# CW312_K82.net
KiCad netlist of a schematic drawn in Altium Designer
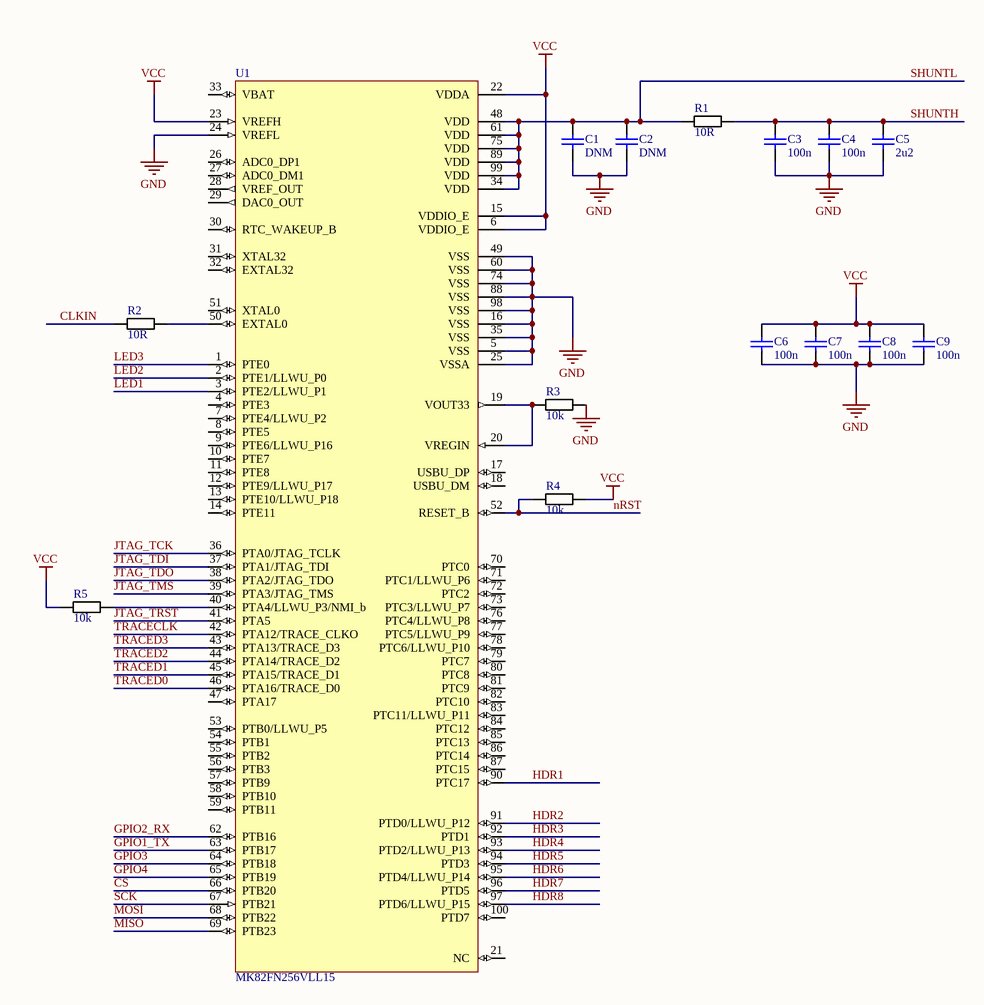
[diagram p0: CW312_K82.SchDoc]

(export (version "E")
  (design (tool "Eeschema 10.0.6"))
  (components
    (comp (ref "C1")
      (value "DNM")
      (footprint "CAPC0603_M")
      (fields (field (name "PART NUMBER") "CCHIP-100n-0603"))
      (libsource (lib "NewAE_AltiumLib") (part "CAP"))
    )
    (comp (ref "C2")
      (value "DNM")
      (footprint "CAPC0603_M")
      (fields (field (name "PART NUMBER") "CCHIP-100n-0603"))
      (libsource (lib "NewAE_AltiumLib") (part "CAP"))
    )
    (comp (ref "C3")
      (value "100n")
      (footprint "CAPC0603_M")
      (description "100n, 0603")
      (fields (field (name "PART NUMBER") "CCHIP-100n-0603"))
      (libsource (lib "NewAE_AltiumLib") (part "CAP"))
    )
    (comp (ref "C4")
      (value "100n")
      (footprint "CAPC0603_M")
      (description "100n, 0603")
      (fields (field (name "PART NUMBER") "CCHIP-100n-0603"))
      (libsource (lib "NewAE_AltiumLib") (part "CAP"))
    )
    (comp (ref "C5")
      (value "2u2")
      (footprint "CAPC0603_M")
      (description "2u2, 0603")
      (fields (field (name "PART NUMBER") "CCHIP-2u2-0603"))
      (libsource (lib "NewAE_AltiumLib") (part "CAP"))
    )
    (comp (ref "C6")
      (value "100n")
      (footprint "CAPC0603_M")
      (description "100n, 0603")
      (fields (field (name "PART NUMBER") "CCHIP-100n-0603"))
      (libsource (lib "NewAE_AltiumLib") (part "CAP"))
    )
    (comp (ref "C7")
      (value "100n")
      (footprint "CAPC0603_M")
      (description "100n, 0603")
      (fields (field (name "PART NUMBER") "CCHIP-100n-0603"))
      (libsource (lib "NewAE_AltiumLib") (part "CAP"))
    )
    (comp (ref "C8")
      (value "100n")
      (footprint "CAPC0603_M")
      (description "100n, 0603")
      (fields (field (name "PART NUMBER") "CCHIP-100n-0603"))
      (libsource (lib "NewAE_AltiumLib") (part "CAP"))
    )
    (comp (ref "C9")
      (value "100n")
      (footprint "CAPC0603_M")
      (description "100n, 0603")
      (fields (field (name "PART NUMBER") "CCHIP-100n-0603"))
      (libsource (lib "NewAE_AltiumLib") (part "CAP"))
    )
    (comp (ref "R1")
      (value "10R")
      (footprint "RESC1608X55N")
      (description "10R res, 0603, 1%, 1/10W")
      (fields (field (name "PART NUMBER") "RCHIP-10R-0603") (field (name "TOLERANCE") "1%"))
      (libsource (lib "NewAE_AltiumLib") (part "RES-EU"))
    )
    (comp (ref "R2")
      (value "10R")
      (footprint "RESC1608X55N")
      (description "10R res, 0603, 1%, 1/10W")
      (fields (field (name "PART NUMBER") "RCHIP-10R-0603") (field (name "TOLERANCE") "1%"))
      (libsource (lib "NewAE_AltiumLib") (part "RES-EU"))
    )
    (comp (ref "R3")
      (value "10k")
      (footprint "RESC1608X55N")
      (description "10k res, 0603, 1%, 1/10W")
      (fields (field (name "PART NUMBER") "RCHIP-10K-0603") (field (name "TOLERANCE") "1%"))
      (libsource (lib "NewAE_AltiumLib") (part "RES-EU"))
    )
    (comp (ref "R4")
      (value "10k")
      (footprint "RESC1608X55N")
      (description "10k res, 0603, 1%, 1/10W")
      (fields (field (name "PART NUMBER") "RCHIP-10K-0603") (field (name "TOLERANCE") "1%"))
      (libsource (lib "NewAE_AltiumLib") (part "RES-EU"))
    )
    (comp (ref "R5")
      (value "10k")
      (footprint "RESC1608X55N")
      (description "10k res, 0603, 1%, 1/10W")
      (fields (field (name "PART NUMBER") "RCHIP-10K-0603") (field (name "TOLERANCE") "1%"))
      (libsource (lib "NewAE_AltiumLib") (part "RES-EU"))
    )
    (comp (ref "U1")
      (value "MK82FN256VLL15")
      (footprint "SQFP50P1600X1600X170-100N")
      (libsource (lib "NewAE_AltiumLib") (part "MK82FN256VLL15"))
    )
  )
  (nets
    (net (code "1") (name "/CLKIN") (class "Default")
      (node (ref "R2") (pin "1") (pinfunction "1_1") (pintype "passive"))
    )
    (net (code "2") (name "/CS") (class "Default")
      (node (ref "U1") (pin "66") (pinfunction "PTB20_66") (pintype "bidirectional"))
    )
    (net (code "3") (name "/GPIO1_TX") (class "Default")
      (node (ref "U1") (pin "63") (pinfunction "PTB17_63") (pintype "bidirectional"))
    )
    (net (code "4") (name "/GPIO2_RX") (class "Default")
      (node (ref "U1") (pin "62") (pinfunction "PTB16_62") (pintype "bidirectional"))
    )
    (net (code "5") (name "/GPIO3") (class "Default")
      (node (ref "U1") (pin "64") (pinfunction "PTB18_64") (pintype "bidirectional"))
    )
    (net (code "6") (name "/GPIO4") (class "Default")
      (node (ref "U1") (pin "65") (pinfunction "PTB19_65") (pintype "bidirectional"))
    )
    (net (code "7") (name "/HDR1") (class "Default")
      (node (ref "U1") (pin "90") (pinfunction "PTC17_90") (pintype "bidirectional"))
    )
    (net (code "8") (name "/HDR2") (class "Default")
      (node (ref "U1") (pin "91") (pinfunction "PTD0/LLWU_P12_91") (pintype "bidirectional"))
    )
    (net (code "9") (name "/HDR3") (class "Default")
      (node (ref "U1") (pin "92") (pinfunction "PTD1_92") (pintype "bidirectional"))
    )
    (net (code "10") (name "/HDR4") (class "Default")
      (node (ref "U1") (pin "93") (pinfunction "PTD2/LLWU_P13_93") (pintype "bidirectional"))
    )
    (net (code "11") (name "/HDR5") (class "Default")
      (node (ref "U1") (pin "94") (pinfunction "PTD3_94") (pintype "bidirectional"))
    )
    (net (code "12") (name "/HDR6") (class "Default")
      (node (ref "U1") (pin "95") (pinfunction "PTD4/LLWU_P14_95") (pintype "bidirectional"))
    )
    (net (code "13") (name "/HDR7") (class "Default")
      (node (ref "U1") (pin "96") (pinfunction "PTD5_96") (pintype "bidirectional"))
    )
    (net (code "14") (name "/HDR8") (class "Default")
      (node (ref "U1") (pin "97") (pinfunction "PTD6/LLWU_P15_97") (pintype "bidirectional"))
    )
    (net (code "15") (name "/JTAG_TCK") (class "Default")
      (node (ref "U1") (pin "36") (pinfunction "PTA0/JTAG_TCLK_36") (pintype "bidirectional"))
    )
    (net (code "16") (name "/JTAG_TDI") (class "Default")
      (node (ref "U1") (pin "37") (pinfunction "PTA1/JTAG_TDI_37") (pintype "bidirectional"))
    )
    (net (code "17") (name "/JTAG_TDO") (class "Default")
      (node (ref "U1") (pin "38") (pinfunction "PTA2/JTAG_TDO_38") (pintype "bidirectional"))
    )
    (net (code "18") (name "/JTAG_TMS") (class "Default")
      (node (ref "U1") (pin "39") (pinfunction "PTA3/JTAG_TMS_39") (pintype "bidirectional"))
    )
    (net (code "19") (name "/JTAG_TRST") (class "Default")
      (node (ref "U1") (pin "41") (pinfunction "PTA5_41") (pintype "bidirectional"))
    )
    (net (code "20") (name "/LED1") (class "Default")
      (node (ref "U1") (pin "3") (pinfunction "PTE2/LLWU_P1_3") (pintype "bidirectional"))
    )
    (net (code "21") (name "/LED2") (class "Default")
      (node (ref "U1") (pin "2") (pinfunction "PTE1/LLWU_P0_2") (pintype "bidirectional"))
    )
    (net (code "22") (name "/LED3") (class "Default")
      (node (ref "U1") (pin "1") (pinfunction "PTE0_1") (pintype "bidirectional"))
    )
    (net (code "23") (name "/MISO") (class "Default")
      (node (ref "U1") (pin "69") (pinfunction "PTB23_69") (pintype "bidirectional"))
    )
    (net (code "24") (name "/MOSI") (class "Default")
      (node (ref "U1") (pin "68") (pinfunction "PTB22_68") (pintype "bidirectional"))
    )
    (net (code "25") (name "/SCK") (class "Default")
      (node (ref "U1") (pin "67") (pinfunction "PTB21_67") (pintype "input"))
    )
    (net (code "26") (name "/SHUNTH") (class "Default")
      (node (ref "C3") (pin "1") (pinfunction "1_1") (pintype "passive"))
      (node (ref "C4") (pin "1") (pinfunction "1_1") (pintype "passive"))
      (node (ref "C5") (pin "1") (pinfunction "1_1") (pintype "passive"))
      (node (ref "R1") (pin "2") (pinfunction "2_2") (pintype "passive"))
    )
    (net (code "27") (name "/SHUNTL") (class "Default")
      (node (ref "C1") (pin "1") (pinfunction "1_1") (pintype "passive"))
      (node (ref "C2") (pin "1") (pinfunction "1_1") (pintype "passive"))
      (node (ref "R1") (pin "1") (pinfunction "1_1") (pintype "passive"))
      (node (ref "U1") (pin "34") (pinfunction "VDD_34") (pintype "power_in"))
      (node (ref "U1") (pin "48") (pinfunction "VDD_48") (pintype "power_in"))
      (node (ref "U1") (pin "61") (pinfunction "VDD_61") (pintype "power_in"))
      (node (ref "U1") (pin "75") (pinfunction "VDD_75") (pintype "power_in"))
      (node (ref "U1") (pin "89") (pinfunction "VDD_89") (pintype "power_in"))
      (node (ref "U1") (pin "99") (pinfunction "VDD_99") (pintype "power_in"))
    )
    (net (code "28") (name "/TRACECLK") (class "Default")
      (node (ref "U1") (pin "42") (pinfunction "PTA12/TRACE_CLKO_42") (pintype "bidirectional"))
    )
    (net (code "29") (name "/TRACED0") (class "Default")
      (node (ref "U1") (pin "46") (pinfunction "PTA16/TRACE_D0_46") (pintype "bidirectional"))
    )
    (net (code "30") (name "/TRACED1") (class "Default")
      (node (ref "U1") (pin "45") (pinfunction "PTA15/TRACE_D1_45") (pintype "bidirectional"))
    )
    (net (code "31") (name "/TRACED2") (class "Default")
      (node (ref "U1") (pin "44") (pinfunction "PTA14/TRACE_D2_44") (pintype "bidirectional"))
    )
    (net (code "32") (name "/TRACED3") (class "Default")
      (node (ref "U1") (pin "43") (pinfunction "PTA13/TRACE_D3_43") (pintype "bidirectional"))
    )
    (net (code "33") (name "/nRST") (class "Default")
      (node (ref "R4") (pin "1") (pinfunction "1_1") (pintype "passive"))
      (node (ref "U1") (pin "52") (pinfunction "RESET_B_52") (pintype "bidirectional"))
    )
    (net (code "34") (name "GND") (class "Default")
      (node (ref "C1") (pin "2") (pinfunction "2_2") (pintype "passive"))
      (node (ref "C2") (pin "2") (pinfunction "2_2") (pintype "passive"))
      (node (ref "C3") (pin "2") (pinfunction "2_2") (pintype "passive"))
      (node (ref "C4") (pin "2") (pinfunction "2_2") (pintype "passive"))
      (node (ref "C5") (pin "2") (pinfunction "2_2") (pintype "passive"))
      (node (ref "C6") (pin "2") (pinfunction "2_2") (pintype "passive"))
      (node (ref "C7") (pin "2") (pinfunction "2_2") (pintype "passive"))
      (node (ref "C8") (pin "2") (pinfunction "2_2") (pintype "passive"))
      (node (ref "C9") (pin "2") (pinfunction "2_2") (pintype "passive"))
      (node (ref "R3") (pin "2") (pinfunction "2_2") (pintype "passive"))
      (node (ref "U1") (pin "16") (pinfunction "VSS_16") (pintype "power_in"))
      (node (ref "U1") (pin "24") (pinfunction "VREFL_24") (pintype "input"))
      (node (ref "U1") (pin "25") (pinfunction "VSSA_25") (pintype "power_in"))
      (node (ref "U1") (pin "35") (pinfunction "VSS_35") (pintype "power_in"))
      (node (ref "U1") (pin "49") (pinfunction "VSS_49") (pintype "power_in"))
      (node (ref "U1") (pin "5") (pinfunction "VSS_5") (pintype "power_in"))
      (node (ref "U1") (pin "60") (pinfunction "VSS_60") (pintype "power_in"))
      (node (ref "U1") (pin "74") (pinfunction "VSS_74") (pintype "power_in"))
      (node (ref "U1") (pin "88") (pinfunction "VSS_88") (pintype "power_in"))
      (node (ref "U1") (pin "98") (pinfunction "VSS_98") (pintype "power_in"))
    )
    (net (code "35") (name "Net-(U1-EXTAL0)") (class "Default")
      (node (ref "R2") (pin "2") (pinfunction "2_2") (pintype "passive"))
      (node (ref "U1") (pin "50") (pinfunction "EXTAL0_50") (pintype "bidirectional"))
    )
    (net (code "36") (name "Net-(U1-PTA4{slash}LLWU_P3{slash}NMI_b)") (class "Default")
      (node (ref "R5") (pin "2") (pinfunction "2_2") (pintype "passive"))
      (node (ref "U1") (pin "40") (pinfunction "PTA4/LLWU_P3/NMI_b_40") (pintype "bidirectional"))
    )
    (net (code "37") (name "Net-(U1-VOUT33)") (class "Default")
      (node (ref "R3") (pin "1") (pinfunction "1_1") (pintype "passive"))
      (node (ref "U1") (pin "19") (pinfunction "VOUT33_19") (pintype "output"))
      (node (ref "U1") (pin "20") (pinfunction "VREGIN_20") (pintype "input"))
    )
    (net (code "38") (name "VCC") (class "Default")
      (node (ref "C6") (pin "1") (pinfunction "1_1") (pintype "passive"))
      (node (ref "C7") (pin "1") (pinfunction "1_1") (pintype "passive"))
      (node (ref "C8") (pin "1") (pinfunction "1_1") (pintype "passive"))
      (node (ref "C9") (pin "1") (pinfunction "1_1") (pintype "passive"))
      (node (ref "R4") (pin "2") (pinfunction "2_2") (pintype "passive"))
      (node (ref "R5") (pin "1") (pinfunction "1_1") (pintype "passive"))
      (node (ref "U1") (pin "15") (pinfunction "VDDIO_E_15") (pintype "power_in"))
      (node (ref "U1") (pin "22") (pinfunction "VDDA_22") (pintype "power_in"))
      (node (ref "U1") (pin "23") (pinfunction "VREFH_23") (pintype "input"))
      (node (ref "U1") (pin "6") (pinfunction "VDDIO_E_6") (pintype "power_in"))
    )
    (net (code "39") (name "unconnected-(U1-ADC0_DM1-Pad27)") (class "Default")
      (node (ref "U1") (pin "27") (pinfunction "ADC0_DM1_27") (pintype "bidirectional"))
    )
    (net (code "40") (name "unconnected-(U1-ADC0_DP1-Pad26)") (class "Default")
      (node (ref "U1") (pin "26") (pinfunction "ADC0_DP1_26") (pintype "bidirectional"))
    )
    (net (code "41") (name "unconnected-(U1-DAC0_OUT-Pad29)") (class "Default")
      (node (ref "U1") (pin "29") (pinfunction "DAC0_OUT_29") (pintype "output"))
    )
    (net (code "42") (name "unconnected-(U1-EXTAL32-Pad32)") (class "Default")
      (node (ref "U1") (pin "32") (pinfunction "EXTAL32_32") (pintype "bidirectional"))
    )
    (net (code "43") (name "unconnected-(U1-NC-Pad21)") (class "Default")
      (node (ref "U1") (pin "21") (pinfunction "NC_21") (pintype "bidirectional"))
    )
    (net (code "44") (name "unconnected-(U1-PTA17-Pad47)") (class "Default")
      (node (ref "U1") (pin "47") (pinfunction "PTA17_47") (pintype "bidirectional"))
    )
    (net (code "45") (name "unconnected-(U1-PTB0{slash}LLWU_P5-Pad53)") (class "Default")
      (node (ref "U1") (pin "53") (pinfunction "PTB0/LLWU_P5_53") (pintype "bidirectional"))
    )
    (net (code "46") (name "unconnected-(U1-PTB1-Pad54)") (class "Default")
      (node (ref "U1") (pin "54") (pinfunction "PTB1_54") (pintype "bidirectional"))
    )
    (net (code "47") (name "unconnected-(U1-PTB2-Pad55)") (class "Default")
      (node (ref "U1") (pin "55") (pinfunction "PTB2_55") (pintype "bidirectional"))
    )
    (net (code "48") (name "unconnected-(U1-PTB3-Pad56)") (class "Default")
      (node (ref "U1") (pin "56") (pinfunction "PTB3_56") (pintype "bidirectional"))
    )
    (net (code "49") (name "unconnected-(U1-PTB9-Pad57)") (class "Default")
      (node (ref "U1") (pin "57") (pinfunction "PTB9_57") (pintype "bidirectional"))
    )
    (net (code "50") (name "unconnected-(U1-PTB10-Pad58)") (class "Default")
      (node (ref "U1") (pin "58") (pinfunction "PTB10_58") (pintype "bidirectional"))
    )
    (net (code "51") (name "unconnected-(U1-PTB11-Pad59)") (class "Default")
      (node (ref "U1") (pin "59") (pinfunction "PTB11_59") (pintype "bidirectional"))
    )
    (net (code "52") (name "unconnected-(U1-PTC0-Pad70)") (class "Default")
      (node (ref "U1") (pin "70") (pinfunction "PTC0_70") (pintype "bidirectional"))
    )
    (net (code "53") (name "unconnected-(U1-PTC1{slash}LLWU_P6-Pad71)") (class "Default")
      (node (ref "U1") (pin "71") (pinfunction "PTC1/LLWU_P6_71") (pintype "bidirectional"))
    )
    (net (code "54") (name "unconnected-(U1-PTC2-Pad72)") (class "Default")
      (node (ref "U1") (pin "72") (pinfunction "PTC2_72") (pintype "bidirectional"))
    )
    (net (code "55") (name "unconnected-(U1-PTC3{slash}LLWU_P7-Pad73)") (class "Default")
      (node (ref "U1") (pin "73") (pinfunction "PTC3/LLWU_P7_73") (pintype "bidirectional"))
    )
    (net (code "56") (name "unconnected-(U1-PTC4{slash}LLWU_P8-Pad76)") (class "Default")
      (node (ref "U1") (pin "76") (pinfunction "PTC4/LLWU_P8_76") (pintype "bidirectional"))
    )
    (net (code "57") (name "unconnected-(U1-PTC5{slash}LLWU_P9-Pad77)") (class "Default")
      (node (ref "U1") (pin "77") (pinfunction "PTC5/LLWU_P9_77") (pintype "bidirectional"))
    )
    (net (code "58") (name "unconnected-(U1-PTC6{slash}LLWU_P10-Pad78)") (class "Default")
      (node (ref "U1") (pin "78") (pinfunction "PTC6/LLWU_P10_78") (pintype "bidirectional"))
    )
    (net (code "59") (name "unconnected-(U1-PTC7-Pad79)") (class "Default")
      (node (ref "U1") (pin "79") (pinfunction "PTC7_79") (pintype "bidirectional"))
    )
    (net (code "60") (name "unconnected-(U1-PTC8-Pad80)") (class "Default")
      (node (ref "U1") (pin "80") (pinfunction "PTC8_80") (pintype "bidirectional"))
    )
    (net (code "61") (name "unconnected-(U1-PTC9-Pad81)") (class "Default")
      (node (ref "U1") (pin "81") (pinfunction "PTC9_81") (pintype "bidirectional"))
    )
    (net (code "62") (name "unconnected-(U1-PTC10-Pad82)") (class "Default")
      (node (ref "U1") (pin "82") (pinfunction "PTC10_82") (pintype "bidirectional"))
    )
    (net (code "63") (name "unconnected-(U1-PTC11{slash}LLWU_P11-Pad83)") (class "Default")
      (node (ref "U1") (pin "83") (pinfunction "PTC11/LLWU_P11_83") (pintype "bidirectional"))
    )
    (net (code "64") (name "unconnected-(U1-PTC12-Pad84)") (class "Default")
      (node (ref "U1") (pin "84") (pinfunction "PTC12_84") (pintype "bidirectional"))
    )
    (net (code "65") (name "unconnected-(U1-PTC13-Pad85)") (class "Default")
      (node (ref "U1") (pin "85") (pinfunction "PTC13_85") (pintype "bidirectional"))
    )
    (net (code "66") (name "unconnected-(U1-PTC14-Pad86)") (class "Default")
      (node (ref "U1") (pin "86") (pinfunction "PTC14_86") (pintype "bidirectional"))
    )
    (net (code "67") (name "unconnected-(U1-PTC15-Pad87)") (class "Default")
      (node (ref "U1") (pin "87") (pinfunction "PTC15_87") (pintype "bidirectional"))
    )
    (net (code "68") (name "unconnected-(U1-PTD7-Pad100)") (class "Default")
      (node (ref "U1") (pin "100") (pinfunction "PTD7_100") (pintype "bidirectional"))
    )
    (net (code "69") (name "unconnected-(U1-PTE3-Pad4)") (class "Default")
      (node (ref "U1") (pin "4") (pinfunction "PTE3_4") (pintype "bidirectional"))
    )
    (net (code "70") (name "unconnected-(U1-PTE4{slash}LLWU_P2-Pad7)") (class "Default")
      (node (ref "U1") (pin "7") (pinfunction "PTE4/LLWU_P2_7") (pintype "bidirectional"))
    )
    (net (code "71") (name "unconnected-(U1-PTE5-Pad8)") (class "Default")
      (node (ref "U1") (pin "8") (pinfunction "PTE5_8") (pintype "bidirectional"))
    )
    (net (code "72") (name "unconnected-(U1-PTE6{slash}LLWU_P16-Pad9)") (class "Default")
      (node (ref "U1") (pin "9") (pinfunction "PTE6/LLWU_P16_9") (pintype "bidirectional"))
    )
    (net (code "73") (name "unconnected-(U1-PTE7-Pad10)") (class "Default")
      (node (ref "U1") (pin "10") (pinfunction "PTE7_10") (pintype "bidirectional"))
    )
    (net (code "74") (name "unconnected-(U1-PTE8-Pad11)") (class "Default")
      (node (ref "U1") (pin "11") (pinfunction "PTE8_11") (pintype "bidirectional"))
    )
    (net (code "75") (name "unconnected-(U1-PTE9{slash}LLWU_P17-Pad12)") (class "Default")
      (node (ref "U1") (pin "12") (pinfunction "PTE9/LLWU_P17_12") (pintype "bidirectional"))
    )
    (net (code "76") (name "unconnected-(U1-PTE10{slash}LLWU_P18-Pad13)") (class "Default")
      (node (ref "U1") (pin "13") (pinfunction "PTE10/LLWU_P18_13") (pintype "bidirectional"))
    )
    (net (code "77") (name "unconnected-(U1-PTE11-Pad14)") (class "Default")
      (node (ref "U1") (pin "14") (pinfunction "PTE11_14") (pintype "bidirectional"))
    )
    (net (code "78") (name "unconnected-(U1-RTC_WAKEUP_B-Pad30)") (class "Default")
      (node (ref "U1") (pin "30") (pinfunction "RTC_WAKEUP_B_30") (pintype "bidirectional"))
    )
    (net (code "79") (name "unconnected-(U1-USBU_DM-Pad18)") (class "Default")
      (node (ref "U1") (pin "18") (pinfunction "USBU_DM_18") (pintype "bidirectional"))
    )
    (net (code "80") (name "unconnected-(U1-USBU_DP-Pad17)") (class "Default")
      (node (ref "U1") (pin "17") (pinfunction "USBU_DP_17") (pintype "bidirectional"))
    )
    (net (code "81") (name "unconnected-(U1-VBAT-Pad33)") (class "Default")
      (node (ref "U1") (pin "33") (pinfunction "VBAT_33") (pintype "bidirectional"))
    )
    (net (code "82") (name "unconnected-(U1-VREF_OUT-Pad28)") (class "Default")
      (node (ref "U1") (pin "28") (pinfunction "VREF_OUT_28") (pintype "output"))
    )
    (net (code "83") (name "unconnected-(U1-XTAL0-Pad51)") (class "Default")
      (node (ref "U1") (pin "51") (pinfunction "XTAL0_51") (pintype "bidirectional"))
    )
    (net (code "84") (name "unconnected-(U1-XTAL32-Pad31)") (class "Default")
      (node (ref "U1") (pin "31") (pinfunction "XTAL32_31") (pintype "bidirectional"))
    )
  )
)
